# plug-v19-delete-value.net
KiCad netlist of a schematic drawn in EAGLE
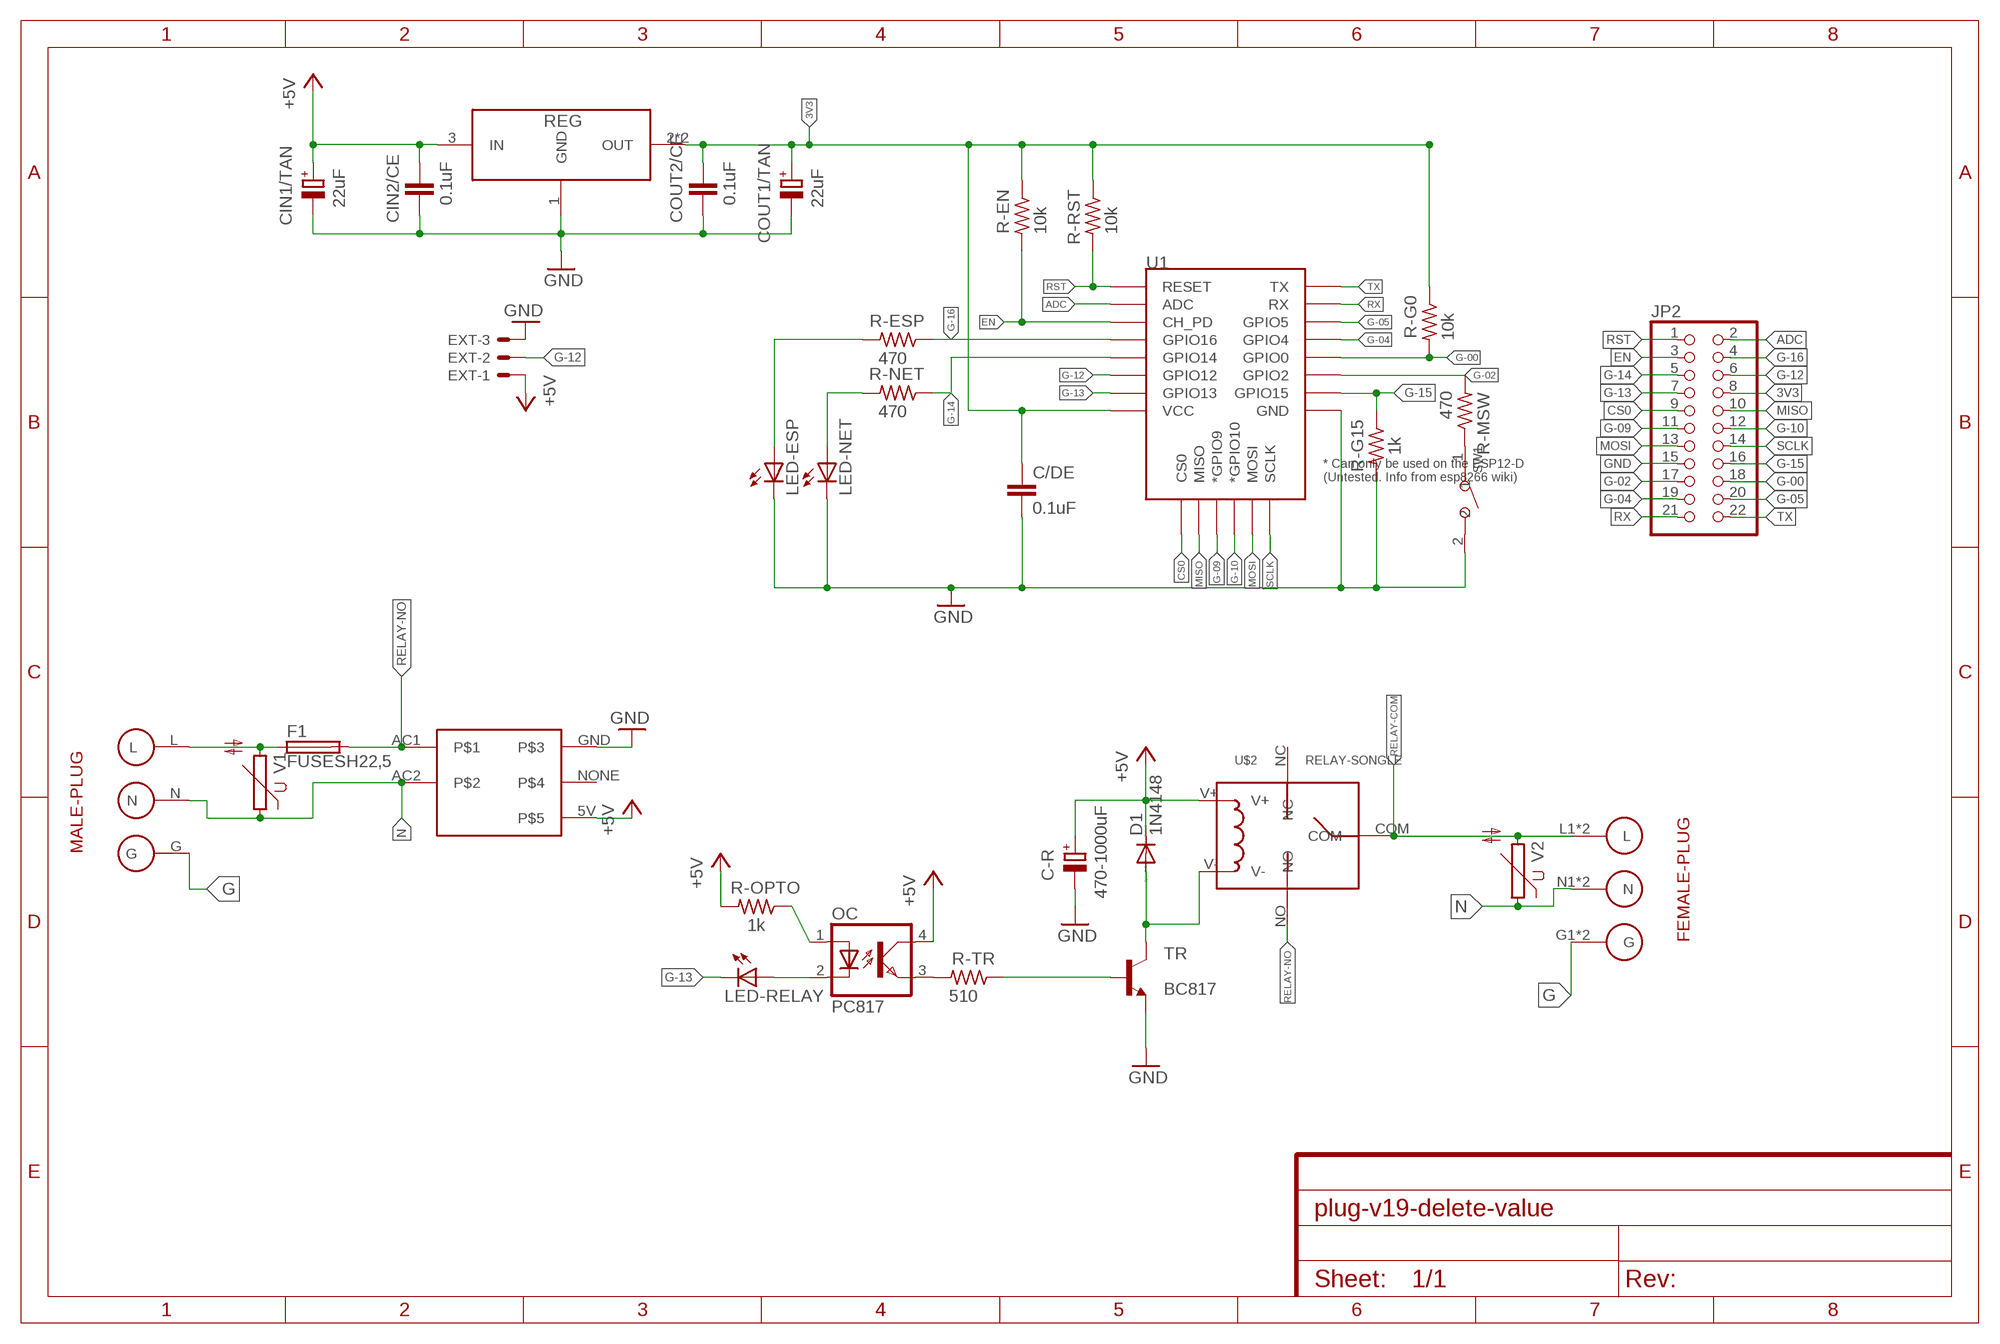
[diagram p0: schematic, sheet 1]

(export (version "E")
  (design (tool "Eeschema 10.0.6"))
  (components
    (comp (ref "C-R")
      (value "470-1000uF")
      (footprint "eagle-import:E3,5-8")
      (libsource (lib "eagle-import") (part "CPOL-EUE3.5-8"))
    )
    (comp (ref "C/DE")
      (value "0.1uF")
      (footprint "eagle-import:C0805")
      (libsource (lib "eagle-import") (part "C-EUC0805"))
    )
    (comp (ref "CIN1/TAN")
      (value "22uF")
      (footprint "eagle-import:B_3528-21R")
      (libsource (lib "eagle-import") (part "CPOL-EUB/3528-21R"))
    )
    (comp (ref "CIN2/CE")
      (value "0.1uF")
      (footprint "eagle-import:C0805K")
      (libsource (lib "eagle-import") (part "C-EUC0805K"))
    )
    (comp (ref "COUT1/TAN")
      (value "22uF")
      (footprint "eagle-import:B_3528-21R")
      (libsource (lib "eagle-import") (part "CPOL-EUB/3528-21R"))
    )
    (comp (ref "COUT2/CE")
      (value "0.1uF")
      (footprint "eagle-import:C0805K")
      (libsource (lib "eagle-import") (part "C-EUC0805K"))
    )
    (comp (ref "D1")
      (value "1N4148")
      (footprint "eagle-import:DO35-7")
      (libsource (lib "eagle-import") (part "1N4148DO35-7"))
    )
    (comp (ref "EXT")
      (value "53048-03")
      (footprint "eagle-import:53048-03")
      (fields (field (name "MF") "WALDOM/MOLEX") (field (name "MPN") "53048-0310"))
      (libsource (lib "eagle-import") (part "53?-03048"))
    )
    (comp (ref "F1")
      (value "FUSESH22,5")
      (footprint "eagle-import:SH22,5")
      (libsource (lib "eagle-import") (part "FUSESH22,5"))
    )
    (comp (ref "JP2")
      (value "PINHD-2X11")
      (footprint "eagle-import:2X11")
      (libsource (lib "eagle-import") (part "PINHD-2X11"))
    )
    (comp (ref "LED-ESP")
      (value "LEDCHIPLED_0805")
      (footprint "eagle-import:CHIPLED_0805")
      (libsource (lib "eagle-import") (part "LEDCHIPLED_0805"))
    )
    (comp (ref "LED-NET")
      (value "LEDCHIPLED_0805")
      (footprint "eagle-import:CHIPLED_0805")
      (libsource (lib "eagle-import") (part "LEDCHIPLED_0805"))
    )
    (comp (ref "LED-RELAY")
      (value "LEDCHIPLED_0805")
      (footprint "eagle-import:CHIPLED_0805")
      (libsource (lib "eagle-import") (part "LEDCHIPLED_0805"))
    )
    (comp (ref "OC")
      (value "PC817")
      (footprint "eagle-import:DIL04")
      (fields (field (name "MPN") "PC817X4J000F"))
      (libsource (lib "eagle-import") (part "PC817"))
    )
    (comp (ref "R-EN")
      (value "10k")
      (footprint "eagle-import:M0805")
      (libsource (lib "eagle-import") (part "R-US_M0805"))
    )
    (comp (ref "R-ESP")
      (value "470")
      (footprint "eagle-import:M0805")
      (libsource (lib "eagle-import") (part "R-US_M0805"))
    )
    (comp (ref "R-G0")
      (value "10k")
      (footprint "eagle-import:M0805")
      (libsource (lib "eagle-import") (part "R-US_M0805"))
    )
    (comp (ref "R-G15")
      (value "1k")
      (footprint "eagle-import:M0805")
      (libsource (lib "eagle-import") (part "R-US_M0805"))
    )
    (comp (ref "R-MSW")
      (value "470")
      (footprint "eagle-import:M0805")
      (libsource (lib "eagle-import") (part "R-US_M0805"))
    )
    (comp (ref "R-NET")
      (value "470")
      (footprint "eagle-import:M0805")
      (libsource (lib "eagle-import") (part "R-US_M0805"))
    )
    (comp (ref "R-OPTO")
      (value "1k")
      (footprint "eagle-import:M0805")
      (libsource (lib "eagle-import") (part "R-US_M0805"))
    )
    (comp (ref "R-RST")
      (value "10k")
      (footprint "eagle-import:M0805")
      (libsource (lib "eagle-import") (part "R-US_M0805"))
    )
    (comp (ref "R-TR")
      (value "510")
      (footprint "eagle-import:M0805")
      (libsource (lib "eagle-import") (part "R-US_M0805"))
    )
    (comp (ref "REG")
      (value "AMS1117-3.3")
      (footprint "eagle-import:SOT-223")
      (libsource (lib "eagle-import") (part "AMS1117-3.3"))
    )
    (comp (ref "SW1")
      (value "DIP-BUTTON(2P-6.0X3.0X4.3MM)-TS-1101F")
      (footprint "eagle-import:SW2-5.0-6.0X3.0X4.3MM")
      (libsource (lib "eagle-import") (part "DIP-BUTTON(2P-6.0X3.0X4.3MM)-TS-1101F"))
    )
    (comp (ref "TR")
      (value "BC817")
      (footprint "eagle-import:SOT23-BEC")
      (libsource (lib "eagle-import") (part "BC817SMD-16"))
    )
    (comp (ref "U$2")
      (value "RELAY-SONGLE")
      (footprint "eagle-import:RELAY-SONGLE")
      (libsource (lib "eagle-import") (part "RELAY-SONGLE"))
    )
    (comp (ref "U$3")
      (value "MALE-PLUG")
      (footprint "eagle-import:MALE-PLUG")
      (libsource (lib "eagle-import") (part "MALE-PLUG"))
    )
    (comp (ref "U$4")
      (value "POWERSUPPLY-5V-700MA")
      (footprint "eagle-import:POWERSUPPLY-5V-700MA")
      (libsource (lib "eagle-import") (part "POWERSUPPLY-5V-700MA"))
    )
    (comp (ref "U$5")
      (value "FEMALE-PLUG")
      (footprint "eagle-import:FEMALE-PLUG")
      (libsource (lib "eagle-import") (part "FEMALE-PLUG"))
    )
    (comp (ref "U1")
      (value "ESP12ESMD")
      (footprint "eagle-import:ESP12E-SMD")
      (libsource (lib "eagle-import") (part "ESP12ESMD"))
    )
    (comp (ref "V1")
      (value "S14K11")
      (footprint "eagle-import:S14K11")
      (libsource (lib "eagle-import") (part "S14K11"))
    )
    (comp (ref "V2")
      (value "S14K11")
      (footprint "eagle-import:S14K11")
      (libsource (lib "eagle-import") (part "S14K11"))
    )
  )
  (nets
    (net (code "1") (name "+5V") (class "Default")
      (node (ref "C-R") (pin "+") (pinfunction "+_+") (pintype "passive"))
      (node (ref "CIN1/TAN") (pin "+") (pinfunction "+_+") (pintype "passive"))
      (node (ref "CIN2/CE") (pin "1") (pinfunction "1_1") (pintype "passive"))
      (node (ref "D1") (pin "C") (pinfunction "C_C") (pintype "passive"))
      (node (ref "EXT") (pin "1") (pinfunction "S_1") (pintype "passive"))
      (node (ref "OC") (pin "4") (pinfunction "COL_4") (pintype "passive"))
      (node (ref "R-OPTO") (pin "2") (pinfunction "2_2") (pintype "passive"))
      (node (ref "REG") (pin "3") (pinfunction "IN_3") (pintype "input"))
      (node (ref "U$2") (pin "V+") (pinfunction "V+_V+") (pintype "bidirectional"))
      (node (ref "U$4") (pin "5V") (pinfunction "P$5_5V") (pintype "bidirectional"))
    )
    (net (code "2") (name "3V3") (class "Default")
      (node (ref "C/DE") (pin "1") (pinfunction "1_1") (pintype "passive"))
      (node (ref "COUT1/TAN") (pin "+") (pinfunction "+_+") (pintype "passive"))
      (node (ref "COUT2/CE") (pin "1") (pinfunction "1_1") (pintype "passive"))
      (node (ref "JP2") (pin "8") (pinfunction "8_8") (pintype "passive"))
      (node (ref "R-EN") (pin "1") (pinfunction "1_1") (pintype "passive"))
      (node (ref "R-G0") (pin "1") (pinfunction "1_1") (pintype "passive"))
      (node (ref "R-RST") (pin "1") (pinfunction "1_1") (pintype "passive"))
      (node (ref "REG") (pin "2") (pinfunction "OUT_2") (pintype "output"))
      (node (ref "REG") (pin "4") (pinfunction "OUT_4") (pintype "output"))
      (node (ref "U1") (pin "VCC") (pinfunction "VCC_VCC") (pintype "bidirectional"))
    )
    (net (code "3") (name "ADC") (class "Default")
      (node (ref "JP2") (pin "2") (pinfunction "2_2") (pintype "passive"))
      (node (ref "U1") (pin "ADC") (pinfunction "ADC_ADC") (pintype "bidirectional"))
    )
    (net (code "4") (name "CS0") (class "Default")
      (node (ref "JP2") (pin "9") (pinfunction "9_9") (pintype "passive"))
      (node (ref "U1") (pin "CS0") (pinfunction "CS0_CS0") (pintype "bidirectional"))
    )
    (net (code "5") (name "EN") (class "Default")
      (node (ref "JP2") (pin "3") (pinfunction "3_3") (pintype "passive"))
      (node (ref "R-EN") (pin "2") (pinfunction "2_2") (pintype "passive"))
      (node (ref "U1") (pin "CH_PD") (pinfunction "CH_PD_CH_PD") (pintype "bidirectional"))
    )
    (net (code "6") (name "G") (class "Default")
      (node (ref "U$3") (pin "G") (pinfunction "G_G") (pintype "bidirectional"))
      (node (ref "U$5") (pin "G1") (pinfunction "G_G1") (pintype "bidirectional"))
      (node (ref "U$5") (pin "G2") (pinfunction "G_G2") (pintype "bidirectional"))
    )
    (net (code "7") (name "G-00") (class "Default")
      (node (ref "JP2") (pin "18") (pinfunction "18_18") (pintype "passive"))
      (node (ref "R-G0") (pin "2") (pinfunction "2_2") (pintype "passive"))
      (node (ref "U1") (pin "GPIO0") (pinfunction "GPIO0_GPIO0") (pintype "bidirectional"))
    )
    (net (code "8") (name "G-02") (class "Default")
      (node (ref "JP2") (pin "17") (pinfunction "17_17") (pintype "passive"))
      (node (ref "R-MSW") (pin "2") (pinfunction "2_2") (pintype "passive"))
      (node (ref "U1") (pin "GPIO2") (pinfunction "GPIO2_GPIO2") (pintype "bidirectional"))
    )
    (net (code "9") (name "G-04") (class "Default")
      (node (ref "JP2") (pin "19") (pinfunction "19_19") (pintype "passive"))
      (node (ref "U1") (pin "GPIO4") (pinfunction "GPIO4_GPIO4") (pintype "bidirectional"))
    )
    (net (code "10") (name "G-05") (class "Default")
      (node (ref "JP2") (pin "20") (pinfunction "20_20") (pintype "passive"))
      (node (ref "U1") (pin "GPIO5") (pinfunction "GPIO5_GPIO5") (pintype "bidirectional"))
    )
    (net (code "11") (name "G-09") (class "Default")
      (node (ref "JP2") (pin "11") (pinfunction "11_11") (pintype "passive"))
      (node (ref "U1") (pin "GPIO9") (pinfunction "*GPIO9_GPIO9") (pintype "bidirectional"))
    )
    (net (code "12") (name "G-10") (class "Default")
      (node (ref "JP2") (pin "12") (pinfunction "12_12") (pintype "passive"))
      (node (ref "U1") (pin "GPIO10") (pinfunction "*GPIO10_GPIO10") (pintype "bidirectional"))
    )
    (net (code "13") (name "G-12") (class "Default")
      (node (ref "EXT") (pin "2") (pinfunction "S_2") (pintype "passive"))
      (node (ref "JP2") (pin "6") (pinfunction "6_6") (pintype "passive"))
      (node (ref "U1") (pin "GPIO12") (pinfunction "GPIO12_GPIO12") (pintype "bidirectional"))
    )
    (net (code "14") (name "G-13") (class "Default")
      (node (ref "JP2") (pin "7") (pinfunction "7_7") (pintype "passive"))
      (node (ref "LED-RELAY") (pin "C") (pinfunction "C_C") (pintype "passive"))
      (node (ref "U1") (pin "GPIO13") (pinfunction "GPIO13_GPIO13") (pintype "bidirectional"))
    )
    (net (code "15") (name "G-14") (class "Default")
      (node (ref "JP2") (pin "5") (pinfunction "5_5") (pintype "passive"))
      (node (ref "R-NET") (pin "1") (pinfunction "1_1") (pintype "passive"))
      (node (ref "U1") (pin "GPIO14") (pinfunction "GPIO14_GPIO14") (pintype "bidirectional"))
    )
    (net (code "16") (name "G-15") (class "Default")
      (node (ref "JP2") (pin "16") (pinfunction "16_16") (pintype "passive"))
      (node (ref "R-G15") (pin "1") (pinfunction "1_1") (pintype "passive"))
      (node (ref "U1") (pin "GPIO15") (pinfunction "GPIO15_GPIO15") (pintype "bidirectional"))
    )
    (net (code "17") (name "G-16") (class "Default")
      (node (ref "JP2") (pin "4") (pinfunction "4_4") (pintype "passive"))
      (node (ref "R-ESP") (pin "1") (pinfunction "1_1") (pintype "passive"))
      (node (ref "U1") (pin "GPIO16") (pinfunction "GPIO16_GPIO16") (pintype "bidirectional"))
    )
    (net (code "18") (name "GND") (class "Default")
      (node (ref "C-R") (pin "-") (pinfunction "-_-") (pintype "passive"))
      (node (ref "C/DE") (pin "2") (pinfunction "2_2") (pintype "passive"))
      (node (ref "CIN1/TAN") (pin "-") (pinfunction "-_-") (pintype "passive"))
      (node (ref "CIN2/CE") (pin "2") (pinfunction "2_2") (pintype "passive"))
      (node (ref "COUT1/TAN") (pin "-") (pinfunction "-_-") (pintype "passive"))
      (node (ref "COUT2/CE") (pin "2") (pinfunction "2_2") (pintype "passive"))
      (node (ref "EXT") (pin "3") (pinfunction "S_3") (pintype "passive"))
      (node (ref "JP2") (pin "15") (pinfunction "15_15") (pintype "passive"))
      (node (ref "LED-ESP") (pin "C") (pinfunction "C_C") (pintype "passive"))
      (node (ref "LED-NET") (pin "C") (pinfunction "C_C") (pintype "passive"))
      (node (ref "R-G15") (pin "2") (pinfunction "2_2") (pintype "passive"))
      (node (ref "REG") (pin "1") (pinfunction "GND_1") (pintype "passive"))
      (node (ref "SW1") (pin "2") (pinfunction "2_2") (pintype "bidirectional"))
      (node (ref "TR") (pin "E") (pinfunction "E_E") (pintype "passive"))
      (node (ref "U$4") (pin "GND") (pinfunction "P$3_GND") (pintype "bidirectional"))
      (node (ref "U1") (pin "GND") (pinfunction "GND_GND") (pintype "bidirectional"))
    )
    (net (code "19") (name "MISO") (class "Default")
      (node (ref "JP2") (pin "10") (pinfunction "10_10") (pintype "passive"))
      (node (ref "U1") (pin "MISO") (pinfunction "MISO_MISO") (pintype "bidirectional"))
    )
    (net (code "20") (name "MOSI") (class "Default")
      (node (ref "JP2") (pin "13") (pinfunction "13_13") (pintype "passive"))
      (node (ref "U1") (pin "MOSI") (pinfunction "MOSI_MOSI") (pintype "bidirectional"))
    )
    (net (code "21") (name "N") (class "Default")
      (node (ref "U$3") (pin "N") (pinfunction "N_N") (pintype "bidirectional"))
      (node (ref "U$4") (pin "AC2") (pinfunction "P$2_AC2") (pintype "bidirectional"))
      (node (ref "U$5") (pin "N1") (pinfunction "N_N1") (pintype "bidirectional"))
      (node (ref "U$5") (pin "N2") (pinfunction "N_N2") (pintype "bidirectional"))
      (node (ref "V1") (pin "1") (pinfunction "1_1") (pintype "passive"))
      (node (ref "V2") (pin "1") (pinfunction "1_1") (pintype "passive"))
    )
    (net (code "22") (name "Net-(D1-PadA)") (class "Default")
      (node (ref "D1") (pin "A") (pinfunction "A_A") (pintype "passive"))
      (node (ref "TR") (pin "C") (pinfunction "C_C") (pintype "passive"))
      (node (ref "U$2") (pin "V-") (pinfunction "V-_V-") (pintype "bidirectional"))
    )
    (net (code "23") (name "Net-(F1-Pad1)") (class "Default")
      (node (ref "F1") (pin "1") (pinfunction "1_1") (pintype "passive"))
      (node (ref "U$3") (pin "L") (pinfunction "L_L") (pintype "bidirectional"))
      (node (ref "V1") (pin "2") (pinfunction "2_2") (pintype "passive"))
    )
    (net (code "24") (name "Net-(LED-ESP-PadA)") (class "Default")
      (node (ref "LED-ESP") (pin "A") (pinfunction "A_A") (pintype "passive"))
      (node (ref "R-ESP") (pin "2") (pinfunction "2_2") (pintype "passive"))
    )
    (net (code "25") (name "Net-(LED-NET-PadA)") (class "Default")
      (node (ref "LED-NET") (pin "A") (pinfunction "A_A") (pintype "passive"))
      (node (ref "R-NET") (pin "2") (pinfunction "2_2") (pintype "passive"))
    )
    (net (code "26") (name "Net-(OC-A)") (class "Default")
      (node (ref "OC") (pin "1") (pinfunction "A_1") (pintype "passive"))
      (node (ref "R-OPTO") (pin "1") (pinfunction "1_1") (pintype "passive"))
    )
    (net (code "27") (name "Net-(OC-C)") (class "Default")
      (node (ref "LED-RELAY") (pin "A") (pinfunction "A_A") (pintype "passive"))
      (node (ref "OC") (pin "2") (pinfunction "C_2") (pintype "passive"))
    )
    (net (code "28") (name "Net-(OC-EMIT)") (class "Default")
      (node (ref "OC") (pin "3") (pinfunction "EMIT_3") (pintype "passive"))
      (node (ref "R-TR") (pin "2") (pinfunction "2_2") (pintype "passive"))
    )
    (net (code "29") (name "Net-(R-MSW-Pad1)") (class "Default")
      (node (ref "R-MSW") (pin "1") (pinfunction "1_1") (pintype "passive"))
      (node (ref "SW1") (pin "1") (pinfunction "1_1") (pintype "bidirectional"))
    )
    (net (code "30") (name "Net-(R-TR-Pad1)") (class "Default")
      (node (ref "R-TR") (pin "1") (pinfunction "1_1") (pintype "passive"))
      (node (ref "TR") (pin "B") (pinfunction "B_B") (pintype "passive"))
    )
    (net (code "31") (name "RELAY-COM") (class "Default")
      (node (ref "U$2") (pin "COM") (pinfunction "COM_COM") (pintype "bidirectional"))
      (node (ref "U$5") (pin "L1") (pinfunction "L_L1") (pintype "bidirectional"))
      (node (ref "U$5") (pin "L2") (pinfunction "L_L2") (pintype "bidirectional"))
      (node (ref "V2") (pin "2") (pinfunction "2_2") (pintype "passive"))
    )
    (net (code "32") (name "RELAY-NO") (class "Default")
      (node (ref "F1") (pin "2") (pinfunction "2_2") (pintype "passive"))
      (node (ref "U$2") (pin "NO") (pinfunction "NO_NO") (pintype "bidirectional"))
      (node (ref "U$4") (pin "AC1") (pinfunction "P$1_AC1") (pintype "bidirectional"))
    )
    (net (code "33") (name "RST") (class "Default")
      (node (ref "JP2") (pin "1") (pinfunction "1_1") (pintype "passive"))
      (node (ref "R-RST") (pin "2") (pinfunction "2_2") (pintype "passive"))
      (node (ref "U1") (pin "RESET") (pinfunction "RESET_RESET") (pintype "bidirectional"))
    )
    (net (code "34") (name "RX") (class "Default")
      (node (ref "JP2") (pin "21") (pinfunction "21_21") (pintype "passive"))
      (node (ref "U1") (pin "RXD0") (pinfunction "RX_RXD0") (pintype "bidirectional"))
    )
    (net (code "35") (name "SCLK") (class "Default")
      (node (ref "JP2") (pin "14") (pinfunction "14_14") (pintype "passive"))
      (node (ref "U1") (pin "SCLK") (pinfunction "SCLK_SCLK") (pintype "bidirectional"))
    )
    (net (code "36") (name "TX") (class "Default")
      (node (ref "JP2") (pin "22") (pinfunction "22_22") (pintype "passive"))
      (node (ref "U1") (pin "TXD0") (pinfunction "TX_TXD0") (pintype "bidirectional"))
    )
    (net (code "37") (name "unconnected-(U$2-PadNC)") (class "Default")
      (node (ref "U$2") (pin "NC") (pinfunction "NC_NC") (pintype "bidirectional"))
    )
    (net (code "38") (name "unconnected-(U$4-P$4-PadNONE)") (class "Default")
      (node (ref "U$4") (pin "NONE") (pinfunction "P$4_NONE") (pintype "bidirectional"))
    )
  )
)
